# rpi_cm3plus_tablet.net
KiCad netlist of a schematic drawn in EAGLE
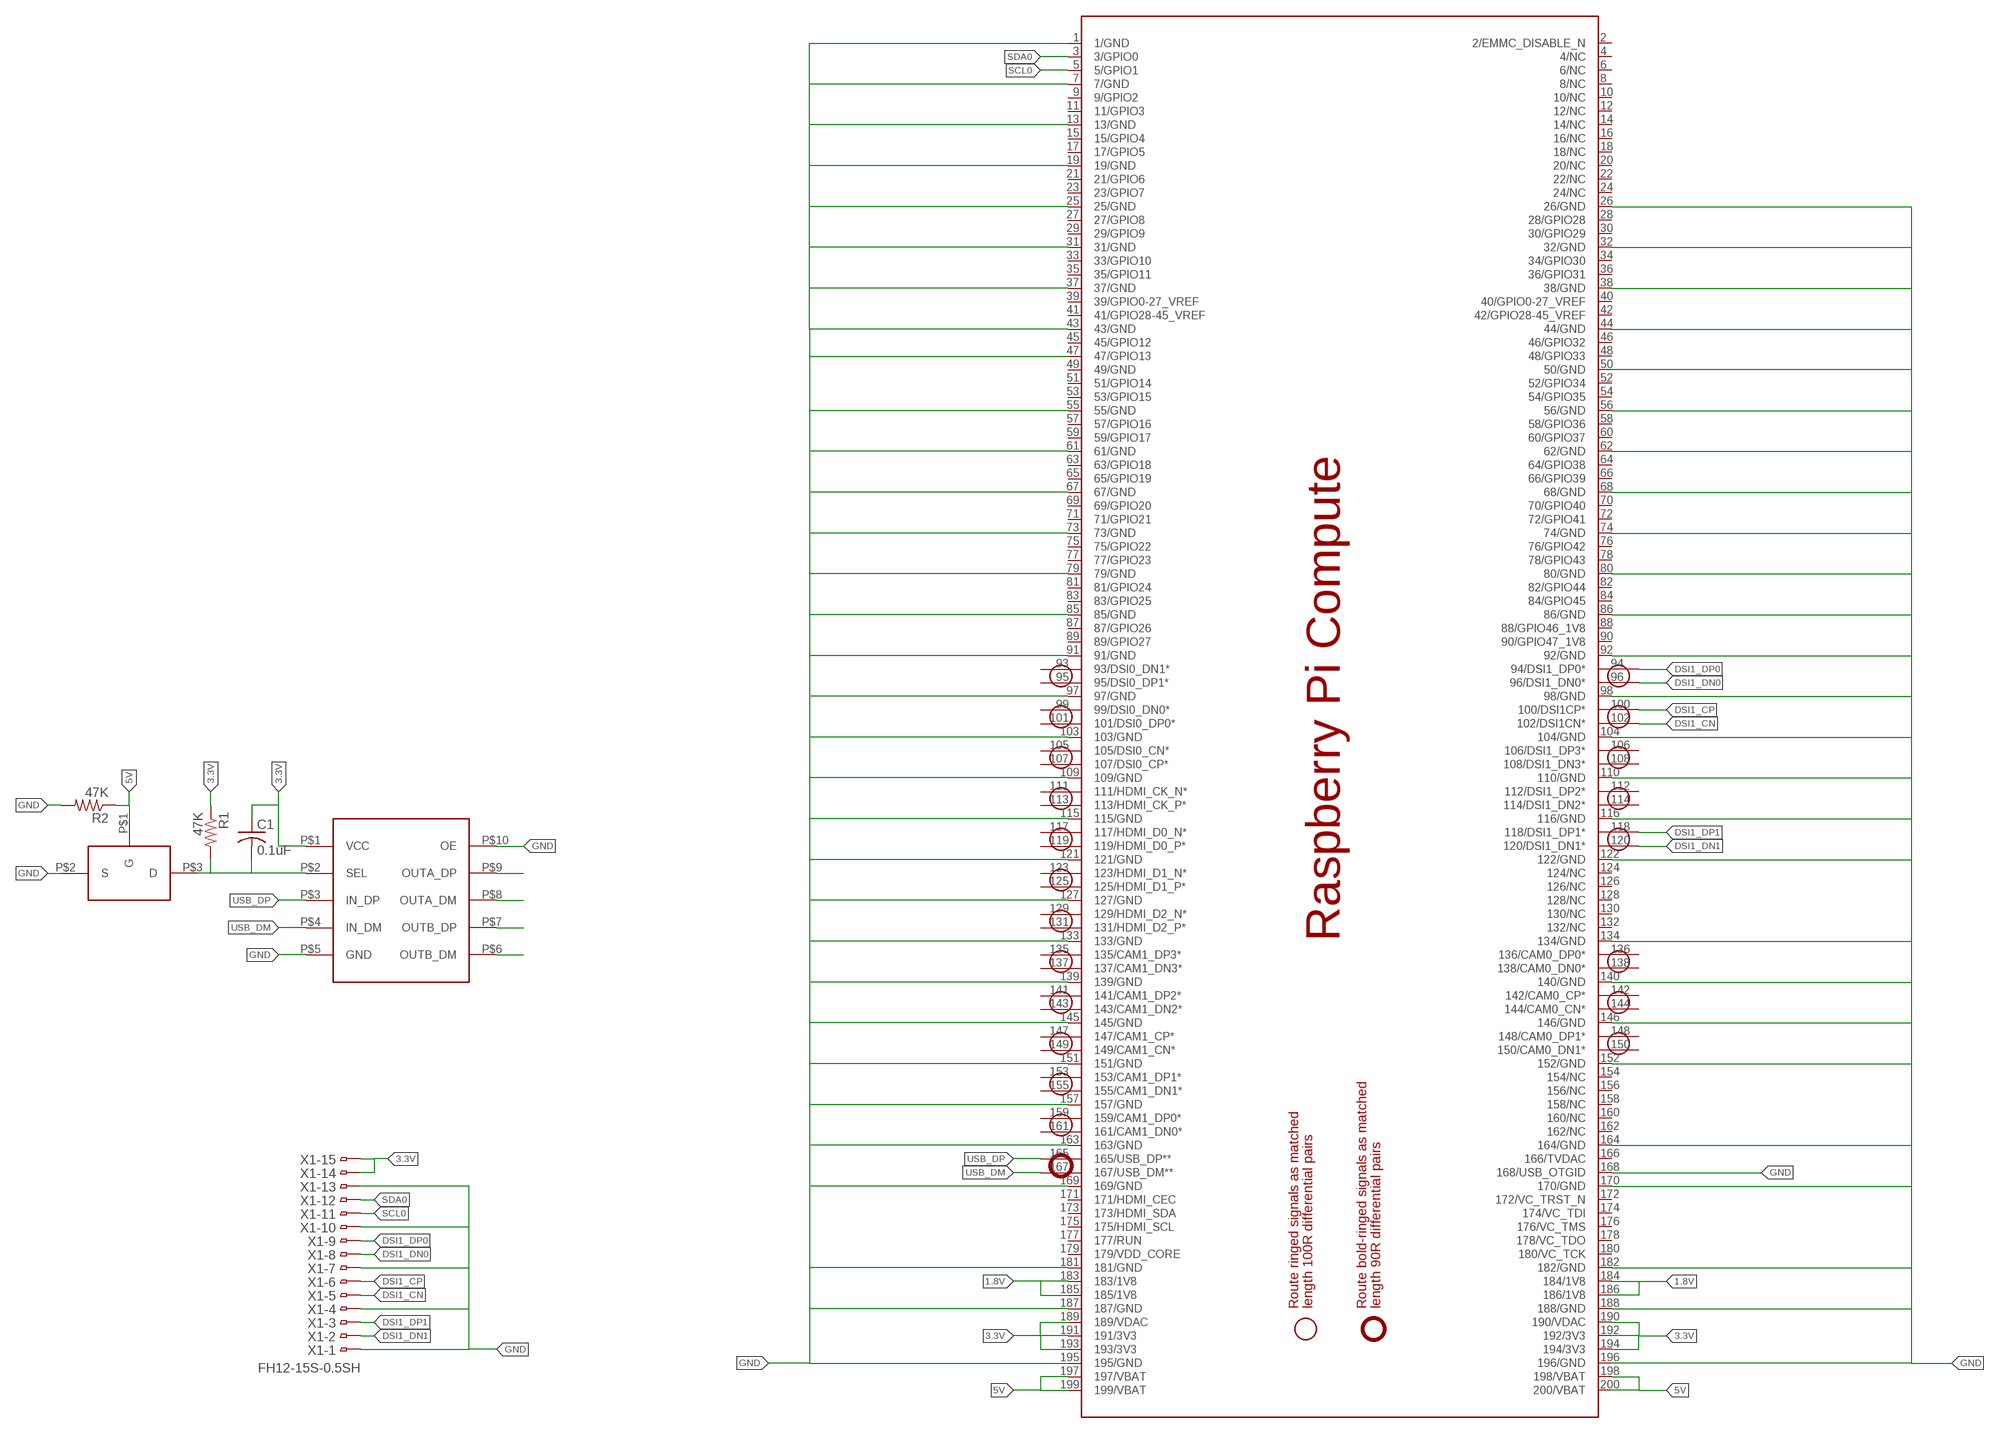
[diagram p0: schematic, sheet 1]

(export (version "E")
  (design (tool "Eeschema 10.0.6"))
  (components
    (comp (ref "C1")
      (value "0.1uF")
      (footprint "eagle-import:C0603K")
      (libsource (lib "eagle-import") (part "C-USC0603K"))
    )
    (comp (ref "PCB1")
      (value "RPI_COMPUTE")
      (footprint "eagle-import:RPI_COMPUTE")
      (libsource (lib "eagle-import") (part "RPI_COMPUTE"))
    )
    (comp (ref "R1")
      (value "47K")
      (footprint "eagle-import:R0603")
      (libsource (lib "eagle-import") (part "R-US_R0603"))
    )
    (comp (ref "R2")
      (value "47K")
      (footprint "eagle-import:R0603")
      (libsource (lib "eagle-import") (part "R-US_R0603"))
    )
    (comp (ref "U$1")
      (value "FSUSB42MUX")
      (footprint "eagle-import:MSOP-10")
      (libsource (lib "eagle-import") (part "FSUSB42MUX"))
    )
    (comp (ref "U$2")
      (value "BSS138-N")
      (footprint "eagle-import:SOT-23")
      (libsource (lib "eagle-import") (part "BSS138-N"))
    )
    (comp (ref "X1")
      (value "FH12-15S-0.5SH")
      (footprint "eagle-import:FH12-15S-0.5SH")
      (libsource (lib "eagle-import") (part "FH12-15S-0.5SH"))
    )
  )
  (nets
    (net (code "1") (name "1.8V") (class "Default")
      (node (ref "PCB1") (pin "183") (pinfunction "183/1V8_183") (pintype "bidirectional"))
      (node (ref "PCB1") (pin "184") (pinfunction "184/1V8_184") (pintype "bidirectional"))
      (node (ref "PCB1") (pin "185") (pinfunction "185/1V8_185") (pintype "bidirectional"))
      (node (ref "PCB1") (pin "186") (pinfunction "186/1V8_186") (pintype "bidirectional"))
    )
    (net (code "2") (name "3.3V") (class "Default")
      (node (ref "C1") (pin "1") (pinfunction "1_1") (pintype "passive"))
      (node (ref "PCB1") (pin "189") (pinfunction "189/VDAC_189") (pintype "bidirectional"))
      (node (ref "PCB1") (pin "190") (pinfunction "190/VDAC_190") (pintype "bidirectional"))
      (node (ref "PCB1") (pin "191") (pinfunction "191/3V3_191") (pintype "bidirectional"))
      (node (ref "PCB1") (pin "192") (pinfunction "192/3V3_192") (pintype "bidirectional"))
      (node (ref "PCB1") (pin "193") (pinfunction "193/3V3_193") (pintype "bidirectional"))
      (node (ref "PCB1") (pin "194") (pinfunction "194/3V3_194") (pintype "bidirectional"))
      (node (ref "R1") (pin "1") (pinfunction "1_1") (pintype "passive"))
      (node (ref "U$1") (pin "P$1") (pinfunction "VCC_P$1") (pintype "bidirectional"))
      (node (ref "X1") (pin "14") (pinfunction "1_14") (pintype "passive"))
      (node (ref "X1") (pin "15") (pinfunction "1_15") (pintype "passive"))
    )
    (net (code "3") (name "5V") (class "Default")
      (node (ref "PCB1") (pin "197") (pinfunction "197/VBAT_197") (pintype "bidirectional"))
      (node (ref "PCB1") (pin "198") (pinfunction "198/VBAT_198") (pintype "bidirectional"))
      (node (ref "PCB1") (pin "199") (pinfunction "199/VBAT_199") (pintype "bidirectional"))
      (node (ref "PCB1") (pin "200") (pinfunction "200/VBAT_200") (pintype "bidirectional"))
      (node (ref "R2") (pin "1") (pinfunction "1_1") (pintype "passive"))
      (node (ref "U$2") (pin "P$1") (pinfunction "G_P$1") (pintype "bidirectional"))
    )
    (net (code "4") (name "DSI1_CN") (class "Default")
      (node (ref "PCB1") (pin "102") (pinfunction "102/DSI1CN*_102") (pintype "bidirectional"))
      (node (ref "X1") (pin "5") (pinfunction "1_5") (pintype "passive"))
    )
    (net (code "5") (name "DSI1_CP") (class "Default")
      (node (ref "PCB1") (pin "100") (pinfunction "100/DSI1CP*_100") (pintype "bidirectional"))
      (node (ref "X1") (pin "6") (pinfunction "1_6") (pintype "passive"))
    )
    (net (code "6") (name "DSI1_DN0") (class "Default")
      (node (ref "PCB1") (pin "96") (pinfunction "96/DSI1_DN0*_96") (pintype "bidirectional"))
      (node (ref "X1") (pin "8") (pinfunction "1_8") (pintype "passive"))
    )
    (net (code "7") (name "DSI1_DN1") (class "Default")
      (node (ref "PCB1") (pin "120") (pinfunction "120/DSI1_DN1*_120") (pintype "bidirectional"))
      (node (ref "X1") (pin "2") (pinfunction "1_2") (pintype "passive"))
    )
    (net (code "8") (name "DSI1_DP0") (class "Default")
      (node (ref "PCB1") (pin "94") (pinfunction "94/DSI1_DP0*_94") (pintype "bidirectional"))
      (node (ref "X1") (pin "9") (pinfunction "1_9") (pintype "passive"))
    )
    (net (code "9") (name "DSI1_DP1") (class "Default")
      (node (ref "PCB1") (pin "118") (pinfunction "118/DSI1_DP1*_118") (pintype "bidirectional"))
      (node (ref "X1") (pin "3") (pinfunction "1_3") (pintype "passive"))
    )
    (net (code "10") (name "GND") (class "Default")
      (node (ref "PCB1") (pin "1") (pinfunction "1/GND_1") (pintype "bidirectional"))
      (node (ref "PCB1") (pin "103") (pinfunction "103/GND_103") (pintype "bidirectional"))
      (node (ref "PCB1") (pin "104") (pinfunction "104/GND_104") (pintype "bidirectional"))
      (node (ref "PCB1") (pin "109") (pinfunction "109/GND_109") (pintype "bidirectional"))
      (node (ref "PCB1") (pin "110") (pinfunction "110/GND_110") (pintype "bidirectional"))
      (node (ref "PCB1") (pin "115") (pinfunction "115/GND_115") (pintype "bidirectional"))
      (node (ref "PCB1") (pin "116") (pinfunction "116/GND_116") (pintype "bidirectional"))
      (node (ref "PCB1") (pin "121") (pinfunction "121/GND_121") (pintype "bidirectional"))
      (node (ref "PCB1") (pin "122") (pinfunction "122/GND_122") (pintype "bidirectional"))
      (node (ref "PCB1") (pin "127") (pinfunction "127/GND_127") (pintype "bidirectional"))
      (node (ref "PCB1") (pin "13") (pinfunction "13/GND_13") (pintype "bidirectional"))
      (node (ref "PCB1") (pin "133") (pinfunction "133/GND_133") (pintype "bidirectional"))
      (node (ref "PCB1") (pin "134") (pinfunction "134/GND_134") (pintype "bidirectional"))
      (node (ref "PCB1") (pin "139") (pinfunction "139/GND_139") (pintype "bidirectional"))
      (node (ref "PCB1") (pin "140") (pinfunction "140/GND_140") (pintype "bidirectional"))
      (node (ref "PCB1") (pin "145") (pinfunction "145/GND_145") (pintype "bidirectional"))
      (node (ref "PCB1") (pin "146") (pinfunction "146/GND_146") (pintype "bidirectional"))
      (node (ref "PCB1") (pin "151") (pinfunction "151/GND_151") (pintype "bidirectional"))
      (node (ref "PCB1") (pin "152") (pinfunction "152/GND_152") (pintype "bidirectional"))
      (node (ref "PCB1") (pin "157") (pinfunction "157/GND_157") (pintype "bidirectional"))
      (node (ref "PCB1") (pin "163") (pinfunction "163/GND_163") (pintype "bidirectional"))
      (node (ref "PCB1") (pin "164") (pinfunction "164/GND_164") (pintype "bidirectional"))
      (node (ref "PCB1") (pin "168") (pinfunction "168/USB_OTGID_168") (pintype "bidirectional"))
      (node (ref "PCB1") (pin "169") (pinfunction "169/GND_169") (pintype "bidirectional"))
      (node (ref "PCB1") (pin "170") (pinfunction "170/GND_170") (pintype "bidirectional"))
      (node (ref "PCB1") (pin "181") (pinfunction "181/GND_181") (pintype "bidirectional"))
      (node (ref "PCB1") (pin "182") (pinfunction "182/GND_182") (pintype "bidirectional"))
      (node (ref "PCB1") (pin "187") (pinfunction "187/GND_187") (pintype "bidirectional"))
      (node (ref "PCB1") (pin "188") (pinfunction "188/GND_188") (pintype "bidirectional"))
      (node (ref "PCB1") (pin "19") (pinfunction "19/GND_19") (pintype "bidirectional"))
      (node (ref "PCB1") (pin "195") (pinfunction "195/GND_195") (pintype "bidirectional"))
      (node (ref "PCB1") (pin "196") (pinfunction "196/GND_196") (pintype "bidirectional"))
      (node (ref "PCB1") (pin "25") (pinfunction "25/GND_25") (pintype "bidirectional"))
      (node (ref "PCB1") (pin "26") (pinfunction "26/GND_26") (pintype "bidirectional"))
      (node (ref "PCB1") (pin "31") (pinfunction "31/GND_31") (pintype "bidirectional"))
      (node (ref "PCB1") (pin "32") (pinfunction "32/GND_32") (pintype "bidirectional"))
      (node (ref "PCB1") (pin "37") (pinfunction "37/GND_37") (pintype "bidirectional"))
      (node (ref "PCB1") (pin "38") (pinfunction "38/GND_38") (pintype "bidirectional"))
      (node (ref "PCB1") (pin "43") (pinfunction "43/GND_43") (pintype "bidirectional"))
      (node (ref "PCB1") (pin "44") (pinfunction "44/GND_44") (pintype "bidirectional"))
      (node (ref "PCB1") (pin "47") (pinfunction "47/GPIO13_47") (pintype "bidirectional"))
      (node (ref "PCB1") (pin "50") (pinfunction "50/GND_50") (pintype "bidirectional"))
      (node (ref "PCB1") (pin "55") (pinfunction "55/GND_55") (pintype "bidirectional"))
      (node (ref "PCB1") (pin "56") (pinfunction "56/GND_56") (pintype "bidirectional"))
      (node (ref "PCB1") (pin "61") (pinfunction "61/GND_61") (pintype "bidirectional"))
      (node (ref "PCB1") (pin "62") (pinfunction "62/GND_62") (pintype "bidirectional"))
      (node (ref "PCB1") (pin "67") (pinfunction "67/GND_67") (pintype "bidirectional"))
      (node (ref "PCB1") (pin "68") (pinfunction "68/GND_68") (pintype "bidirectional"))
      (node (ref "PCB1") (pin "7") (pinfunction "7/GND_7") (pintype "bidirectional"))
      (node (ref "PCB1") (pin "73") (pinfunction "73/GND_73") (pintype "bidirectional"))
      (node (ref "PCB1") (pin "74") (pinfunction "74/GND_74") (pintype "bidirectional"))
      (node (ref "PCB1") (pin "79") (pinfunction "79/GND_79") (pintype "bidirectional"))
      (node (ref "PCB1") (pin "80") (pinfunction "80/GND_80") (pintype "bidirectional"))
      (node (ref "PCB1") (pin "85") (pinfunction "85/GND_85") (pintype "bidirectional"))
      (node (ref "PCB1") (pin "86") (pinfunction "86/GND_86") (pintype "bidirectional"))
      (node (ref "PCB1") (pin "91") (pinfunction "91/GND_91") (pintype "bidirectional"))
      (node (ref "PCB1") (pin "92") (pinfunction "92/GND_92") (pintype "bidirectional"))
      (node (ref "PCB1") (pin "97") (pinfunction "97/GND_97") (pintype "bidirectional"))
      (node (ref "PCB1") (pin "98") (pinfunction "98/GND_98") (pintype "bidirectional"))
      (node (ref "R2") (pin "2") (pinfunction "2_2") (pintype "passive"))
      (node (ref "U$1") (pin "P$10") (pinfunction "OE_P$10") (pintype "bidirectional"))
      (node (ref "U$1") (pin "P$5") (pinfunction "GND_P$5") (pintype "bidirectional"))
      (node (ref "U$2") (pin "P$2") (pinfunction "S_P$2") (pintype "bidirectional"))
      (node (ref "X1") (pin "1") (pinfunction "1_1") (pintype "passive"))
      (node (ref "X1") (pin "10") (pinfunction "1_10") (pintype "passive"))
      (node (ref "X1") (pin "13") (pinfunction "1_13") (pintype "passive"))
      (node (ref "X1") (pin "4") (pinfunction "1_4") (pintype "passive"))
      (node (ref "X1") (pin "7") (pinfunction "1_7") (pintype "passive"))
    )
    (net (code "11") (name "Net-(U$1-SEL)") (class "Default")
      (node (ref "C1") (pin "2") (pinfunction "2_2") (pintype "passive"))
      (node (ref "R1") (pin "2") (pinfunction "2_2") (pintype "passive"))
      (node (ref "U$1") (pin "P$2") (pinfunction "SEL_P$2") (pintype "bidirectional"))
      (node (ref "U$2") (pin "P$3") (pinfunction "D_P$3") (pintype "bidirectional"))
    )
    (net (code "12") (name "SCL0") (class "Default")
      (node (ref "PCB1") (pin "5") (pinfunction "5/GPIO1_5") (pintype "bidirectional"))
      (node (ref "X1") (pin "11") (pinfunction "1_11") (pintype "passive"))
    )
    (net (code "13") (name "SDA0") (class "Default")
      (node (ref "PCB1") (pin "3") (pinfunction "3/GPIO0_3") (pintype "bidirectional"))
      (node (ref "X1") (pin "12") (pinfunction "1_12") (pintype "passive"))
    )
    (net (code "14") (name "USB_DM") (class "Default")
      (node (ref "PCB1") (pin "167") (pinfunction "167/USB_DM**_167") (pintype "bidirectional"))
      (node (ref "U$1") (pin "P$4") (pinfunction "IN_DM_P$4") (pintype "bidirectional"))
    )
    (net (code "15") (name "USB_DP") (class "Default")
      (node (ref "PCB1") (pin "165") (pinfunction "165/USB_DP**_165") (pintype "bidirectional"))
      (node (ref "U$1") (pin "P$3") (pinfunction "IN_DP_P$3") (pintype "bidirectional"))
    )
    (net (code "16") (name "unconnected-(PCB1-2{slash}EMMC_DISABLE_N-Pad2)") (class "Default")
      (node (ref "PCB1") (pin "2") (pinfunction "2/EMMC_DISABLE_N_2") (pintype "bidirectional"))
    )
    (net (code "17") (name "unconnected-(PCB1-4{slash}NC-Pad4)") (class "Default")
      (node (ref "PCB1") (pin "4") (pinfunction "4/NC_4") (pintype "bidirectional"))
    )
    (net (code "18") (name "unconnected-(PCB1-6{slash}NC-Pad6)") (class "Default")
      (node (ref "PCB1") (pin "6") (pinfunction "6/NC_6") (pintype "bidirectional"))
    )
    (net (code "19") (name "unconnected-(PCB1-8{slash}NC-Pad8)") (class "Default")
      (node (ref "PCB1") (pin "8") (pinfunction "8/NC_8") (pintype "bidirectional"))
    )
    (net (code "20") (name "unconnected-(PCB1-9{slash}GPIO2-Pad9)") (class "Default")
      (node (ref "PCB1") (pin "9") (pinfunction "9/GPIO2_9") (pintype "bidirectional"))
    )
    (net (code "21") (name "unconnected-(PCB1-10{slash}NC-Pad10)") (class "Default")
      (node (ref "PCB1") (pin "10") (pinfunction "10/NC_10") (pintype "bidirectional"))
    )
    (net (code "22") (name "unconnected-(PCB1-11{slash}GPIO3-Pad11)") (class "Default")
      (node (ref "PCB1") (pin "11") (pinfunction "11/GPIO3_11") (pintype "bidirectional"))
    )
    (net (code "23") (name "unconnected-(PCB1-12{slash}NC-Pad12)") (class "Default")
      (node (ref "PCB1") (pin "12") (pinfunction "12/NC_12") (pintype "bidirectional"))
    )
    (net (code "24") (name "unconnected-(PCB1-14{slash}NC-Pad14)") (class "Default")
      (node (ref "PCB1") (pin "14") (pinfunction "14/NC_14") (pintype "bidirectional"))
    )
    (net (code "25") (name "unconnected-(PCB1-15{slash}GPIO4-Pad15)") (class "Default")
      (node (ref "PCB1") (pin "15") (pinfunction "15/GPIO4_15") (pintype "bidirectional"))
    )
    (net (code "26") (name "unconnected-(PCB1-16{slash}NC-Pad16)") (class "Default")
      (node (ref "PCB1") (pin "16") (pinfunction "16/NC_16") (pintype "bidirectional"))
    )
    (net (code "27") (name "unconnected-(PCB1-17{slash}GPIO5-Pad17)") (class "Default")
      (node (ref "PCB1") (pin "17") (pinfunction "17/GPIO5_17") (pintype "bidirectional"))
    )
    (net (code "28") (name "unconnected-(PCB1-18{slash}NC-Pad18)") (class "Default")
      (node (ref "PCB1") (pin "18") (pinfunction "18/NC_18") (pintype "bidirectional"))
    )
    (net (code "29") (name "unconnected-(PCB1-20{slash}NC-Pad20)") (class "Default")
      (node (ref "PCB1") (pin "20") (pinfunction "20/NC_20") (pintype "bidirectional"))
    )
    (net (code "30") (name "unconnected-(PCB1-21{slash}GPIO6-Pad21)") (class "Default")
      (node (ref "PCB1") (pin "21") (pinfunction "21/GPIO6_21") (pintype "bidirectional"))
    )
    (net (code "31") (name "unconnected-(PCB1-22{slash}NC-Pad22)") (class "Default")
      (node (ref "PCB1") (pin "22") (pinfunction "22/NC_22") (pintype "bidirectional"))
    )
    (net (code "32") (name "unconnected-(PCB1-23{slash}GPIO7-Pad23)") (class "Default")
      (node (ref "PCB1") (pin "23") (pinfunction "23/GPIO7_23") (pintype "bidirectional"))
    )
    (net (code "33") (name "unconnected-(PCB1-24{slash}NC-Pad24)") (class "Default")
      (node (ref "PCB1") (pin "24") (pinfunction "24/NC_24") (pintype "bidirectional"))
    )
    (net (code "34") (name "unconnected-(PCB1-27{slash}GPIO8-Pad27)") (class "Default")
      (node (ref "PCB1") (pin "27") (pinfunction "27/GPIO8_27") (pintype "bidirectional"))
    )
    (net (code "35") (name "unconnected-(PCB1-28{slash}GPIO28-Pad28)") (class "Default")
      (node (ref "PCB1") (pin "28") (pinfunction "28/GPIO28_28") (pintype "bidirectional"))
    )
    (net (code "36") (name "unconnected-(PCB1-29{slash}GPIO9-Pad29)") (class "Default")
      (node (ref "PCB1") (pin "29") (pinfunction "29/GPIO9_29") (pintype "bidirectional"))
    )
    (net (code "37") (name "unconnected-(PCB1-30{slash}GPIO29-Pad30)") (class "Default")
      (node (ref "PCB1") (pin "30") (pinfunction "30/GPIO29_30") (pintype "bidirectional"))
    )
    (net (code "38") (name "unconnected-(PCB1-33{slash}GPIO10-Pad33)") (class "Default")
      (node (ref "PCB1") (pin "33") (pinfunction "33/GPIO10_33") (pintype "bidirectional"))
    )
    (net (code "39") (name "unconnected-(PCB1-34{slash}GPIO30-Pad34)") (class "Default")
      (node (ref "PCB1") (pin "34") (pinfunction "34/GPIO30_34") (pintype "bidirectional"))
    )
    (net (code "40") (name "unconnected-(PCB1-35{slash}GPIO11-Pad35)") (class "Default")
      (node (ref "PCB1") (pin "35") (pinfunction "35/GPIO11_35") (pintype "bidirectional"))
    )
    (net (code "41") (name "unconnected-(PCB1-36{slash}GPIO31-Pad36)") (class "Default")
      (node (ref "PCB1") (pin "36") (pinfunction "36/GPIO31_36") (pintype "bidirectional"))
    )
    (net (code "42") (name "unconnected-(PCB1-39{slash}GPIO0-27_VREF-Pad39)") (class "Default")
      (node (ref "PCB1") (pin "39") (pinfunction "39/GPIO0-27_VREF_39") (pintype "bidirectional"))
    )
    (net (code "43") (name "unconnected-(PCB1-40{slash}GPIO0-27_VREF-Pad40)") (class "Default")
      (node (ref "PCB1") (pin "40") (pinfunction "40/GPIO0-27_VREF_40") (pintype "bidirectional"))
    )
    (net (code "44") (name "unconnected-(PCB1-41{slash}GPIO28-45_VREF-Pad41)") (class "Default")
      (node (ref "PCB1") (pin "41") (pinfunction "41/GPIO28-45_VREF_41") (pintype "bidirectional"))
    )
    (net (code "45") (name "unconnected-(PCB1-42{slash}GPIO28-45_VREF-Pad42)") (class "Default")
      (node (ref "PCB1") (pin "42") (pinfunction "42/GPIO28-45_VREF_42") (pintype "bidirectional"))
    )
    (net (code "46") (name "unconnected-(PCB1-45{slash}GPIO12-Pad45)") (class "Default")
      (node (ref "PCB1") (pin "45") (pinfunction "45/GPIO12_45") (pintype "bidirectional"))
    )
    (net (code "47") (name "unconnected-(PCB1-46{slash}GPIO32-Pad46)") (class "Default")
      (node (ref "PCB1") (pin "46") (pinfunction "46/GPIO32_46") (pintype "bidirectional"))
    )
    (net (code "48") (name "unconnected-(PCB1-48{slash}GPIO33-Pad48)") (class "Default")
      (node (ref "PCB1") (pin "48") (pinfunction "48/GPIO33_48") (pintype "bidirectional"))
    )
    (net (code "49") (name "unconnected-(PCB1-49{slash}GND-Pad49)") (class "Default")
      (node (ref "PCB1") (pin "49") (pinfunction "49/GND_49") (pintype "bidirectional"))
    )
    (net (code "50") (name "unconnected-(PCB1-51{slash}GPIO14-Pad51)") (class "Default")
      (node (ref "PCB1") (pin "51") (pinfunction "51/GPIO14_51") (pintype "bidirectional"))
    )
    (net (code "51") (name "unconnected-(PCB1-52{slash}GPIO34-Pad52)") (class "Default")
      (node (ref "PCB1") (pin "52") (pinfunction "52/GPIO34_52") (pintype "bidirectional"))
    )
    (net (code "52") (name "unconnected-(PCB1-53{slash}GPIO15-Pad53)") (class "Default")
      (node (ref "PCB1") (pin "53") (pinfunction "53/GPIO15_53") (pintype "bidirectional"))
    )
    (net (code "53") (name "unconnected-(PCB1-54{slash}GPIO35-Pad54)") (class "Default")
      (node (ref "PCB1") (pin "54") (pinfunction "54/GPIO35_54") (pintype "bidirectional"))
    )
    (net (code "54") (name "unconnected-(PCB1-57{slash}GPIO16-Pad57)") (class "Default")
      (node (ref "PCB1") (pin "57") (pinfunction "57/GPIO16_57") (pintype "bidirectional"))
    )
    (net (code "55") (name "unconnected-(PCB1-58{slash}GPIO36-Pad58)") (class "Default")
      (node (ref "PCB1") (pin "58") (pinfunction "58/GPIO36_58") (pintype "bidirectional"))
    )
    (net (code "56") (name "unconnected-(PCB1-59{slash}GPIO17-Pad59)") (class "Default")
      (node (ref "PCB1") (pin "59") (pinfunction "59/GPIO17_59") (pintype "bidirectional"))
    )
    (net (code "57") (name "unconnected-(PCB1-60{slash}GPIO37-Pad60)") (class "Default")
      (node (ref "PCB1") (pin "60") (pinfunction "60/GPIO37_60") (pintype "bidirectional"))
    )
    (net (code "58") (name "unconnected-(PCB1-63{slash}GPIO18-Pad63)") (class "Default")
      (node (ref "PCB1") (pin "63") (pinfunction "63/GPIO18_63") (pintype "bidirectional"))
    )
    (net (code "59") (name "unconnected-(PCB1-64{slash}GPIO38-Pad64)") (class "Default")
      (node (ref "PCB1") (pin "64") (pinfunction "64/GPIO38_64") (pintype "bidirectional"))
    )
    (net (code "60") (name "unconnected-(PCB1-65{slash}GPIO19-Pad65)") (class "Default")
      (node (ref "PCB1") (pin "65") (pinfunction "65/GPIO19_65") (pintype "bidirectional"))
    )
    (net (code "61") (name "unconnected-(PCB1-66{slash}GPIO39-Pad66)") (class "Default")
      (node (ref "PCB1") (pin "66") (pinfunction "66/GPIO39_66") (pintype "bidirectional"))
    )
    (net (code "62") (name "unconnected-(PCB1-69{slash}GPIO20-Pad69)") (class "Default")
      (node (ref "PCB1") (pin "69") (pinfunction "69/GPIO20_69") (pintype "bidirectional"))
    )
    (net (code "63") (name "unconnected-(PCB1-70{slash}GPIO40-Pad70)") (class "Default")
      (node (ref "PCB1") (pin "70") (pinfunction "70/GPIO40_70") (pintype "bidirectional"))
    )
    (net (code "64") (name "unconnected-(PCB1-71{slash}GPIO21-Pad71)") (class "Default")
      (node (ref "PCB1") (pin "71") (pinfunction "71/GPIO21_71") (pintype "bidirectional"))
    )
    (net (code "65") (name "unconnected-(PCB1-72{slash}GPIO41-Pad72)") (class "Default")
      (node (ref "PCB1") (pin "72") (pinfunction "72/GPIO41_72") (pintype "bidirectional"))
    )
    (net (code "66") (name "unconnected-(PCB1-75{slash}GPIO22-Pad75)") (class "Default")
      (node (ref "PCB1") (pin "75") (pinfunction "75/GPIO22_75") (pintype "bidirectional"))
    )
    (net (code "67") (name "unconnected-(PCB1-76{slash}GPIO42-Pad76)") (class "Default")
      (node (ref "PCB1") (pin "76") (pinfunction "76/GPIO42_76") (pintype "bidirectional"))
    )
    (net (code "68") (name "unconnected-(PCB1-77{slash}GPIO23-Pad77)") (class "Default")
      (node (ref "PCB1") (pin "77") (pinfunction "77/GPIO23_77") (pintype "bidirectional"))
    )
    (net (code "69") (name "unconnected-(PCB1-78{slash}GPIO43-Pad78)") (class "Default")
      (node (ref "PCB1") (pin "78") (pinfunction "78/GPIO43_78") (pintype "bidirectional"))
    )
    (net (code "70") (name "unconnected-(PCB1-81{slash}GPIO24-Pad81)") (class "Default")
      (node (ref "PCB1") (pin "81") (pinfunction "81/GPIO24_81") (pintype "bidirectional"))
    )
    (net (code "71") (name "unconnected-(PCB1-82{slash}GPIO44-Pad82)") (class "Default")
      (node (ref "PCB1") (pin "82") (pinfunction "82/GPIO44_82") (pintype "bidirectional"))
    )
    (net (code "72") (name "unconnected-(PCB1-83{slash}GPIO25-Pad83)") (class "Default")
      (node (ref "PCB1") (pin "83") (pinfunction "83/GPIO25_83") (pintype "bidirectional"))
    )
    (net (code "73") (name "unconnected-(PCB1-84{slash}GPIO45-Pad84)") (class "Default")
      (node (ref "PCB1") (pin "84") (pinfunction "84/GPIO45_84") (pintype "bidirectional"))
    )
    (net (code "74") (name "unconnected-(PCB1-87{slash}GPIO26-Pad87)") (class "Default")
      (node (ref "PCB1") (pin "87") (pinfunction "87/GPIO26_87") (pintype "bidirectional"))
    )
    (net (code "75") (name "unconnected-(PCB1-88{slash}GPIO46_1V8-Pad88)") (class "Default")
      (node (ref "PCB1") (pin "88") (pinfunction "88/GPIO46_1V8_88") (pintype "bidirectional"))
    )
    (net (code "76") (name "unconnected-(PCB1-89{slash}GPIO27-Pad89)") (class "Default")
      (node (ref "PCB1") (pin "89") (pinfunction "89/GPIO27_89") (pintype "bidirectional"))
    )
    (net (code "77") (name "unconnected-(PCB1-90{slash}GPIO47_1V8-Pad90)") (class "Default")
      (node (ref "PCB1") (pin "90") (pinfunction "90/GPIO47_1V8_90") (pintype "bidirectional"))
    )
    (net (code "78") (name "unconnected-(PCB1-93{slash}DSI0_DN1*-Pad93)") (class "Default")
      (node (ref "PCB1") (pin "93") (pinfunction "93/DSI0_DN1*_93") (pintype "bidirectional"))
    )
    (net (code "79") (name "unconnected-(PCB1-95{slash}DSI0_DP1*-Pad95)") (class "Default")
      (node (ref "PCB1") (pin "95") (pinfunction "95/DSI0_DP1*_95") (pintype "bidirectional"))
    )
    (net (code "80") (name "unconnected-(PCB1-99{slash}DSI0_DN0*-Pad99)") (class "Default")
      (node (ref "PCB1") (pin "99") (pinfunction "99/DSI0_DN0*_99") (pintype "bidirectional"))
    )
    (net (code "81") (name "unconnected-(PCB1-101{slash}DSI0_DP0*-Pad101)") (class "Default")
      (node (ref "PCB1") (pin "101") (pinfunction "101/DSI0_DP0*_101") (pintype "bidirectional"))
    )
    (net (code "82") (name "unconnected-(PCB1-105{slash}DSI0_CN*-Pad105)") (class "Default")
      (node (ref "PCB1") (pin "105") (pinfunction "105/DSI0_CN*_105") (pintype "bidirectional"))
    )
    (net (code "83") (name "unconnected-(PCB1-106{slash}DSI1_DP3*-Pad106)") (class "Default")
      (node (ref "PCB1") (pin "106") (pinfunction "106/DSI1_DP3*_106") (pintype "bidirectional"))
    )
    (net (code "84") (name "unconnected-(PCB1-107{slash}DSI0_CP*-Pad107)") (class "Default")
      (node (ref "PCB1") (pin "107") (pinfunction "107/DSI0_CP*_107") (pintype "bidirectional"))
    )
    (net (code "85") (name "unconnected-(PCB1-108{slash}DSI1_DN3*-Pad108)") (class "Default")
      (node (ref "PCB1") (pin "108") (pinfunction "108/DSI1_DN3*_108") (pintype "bidirectional"))
    )
    (net (code "86") (name "unconnected-(PCB1-111{slash}HDMI_CK_N*-Pad111)") (class "Default")
      (node (ref "PCB1") (pin "111") (pinfunction "111/HDMI_CK_N*_111") (pintype "bidirectional"))
    )
    (net (code "87") (name "unconnected-(PCB1-112{slash}DSI1_DP2*-Pad112)") (class "Default")
      (node (ref "PCB1") (pin "112") (pinfunction "112/DSI1_DP2*_112") (pintype "bidirectional"))
    )
    (net (code "88") (name "unconnected-(PCB1-113{slash}HDMI_CK_P*-Pad113)") (class "Default")
      (node (ref "PCB1") (pin "113") (pinfunction "113/HDMI_CK_P*_113") (pintype "bidirectional"))
    )
    (net (code "89") (name "unconnected-(PCB1-114{slash}DSI1_DN2*-Pad114)") (class "Default")
      (node (ref "PCB1") (pin "114") (pinfunction "114/DSI1_DN2*_114") (pintype "bidirectional"))
    )
    (net (code "90") (name "unconnected-(PCB1-117{slash}HDMI_D0_N*-Pad117)") (class "Default")
      (node (ref "PCB1") (pin "117") (pinfunction "117/HDMI_D0_N*_117") (pintype "bidirectional"))
    )
    (net (code "91") (name "unconnected-(PCB1-119{slash}HDMI_D0_P*-Pad119)") (class "Default")
      (node (ref "PCB1") (pin "119") (pinfunction "119/HDMI_D0_P*_119") (pintype "bidirectional"))
    )
    (net (code "92") (name "unconnected-(PCB1-123{slash}HDMI_D1_N*-Pad123)") (class "Default")
      (node (ref "PCB1") (pin "123") (pinfunction "123/HDMI_D1_N*_123") (pintype "bidirectional"))
    )
    (net (code "93") (name "unconnected-(PCB1-124{slash}NC-Pad124)") (class "Default")
      (node (ref "PCB1") (pin "124") (pinfunction "124/NC_124") (pintype "bidirectional"))
    )
    (net (code "94") (name "unconnected-(PCB1-125{slash}HDMI_D1_P*-Pad125)") (class "Default")
      (node (ref "PCB1") (pin "125") (pinfunction "125/HDMI_D1_P*_125") (pintype "bidirectional"))
    )
    (net (code "95") (name "unconnected-(PCB1-126{slash}NC-Pad126)") (class "Default")
      (node (ref "PCB1") (pin "126") (pinfunction "126/NC_126") (pintype "bidirectional"))
    )
    (net (code "96") (name "unconnected-(PCB1-128{slash}NC-Pad128)") (class "Default")
      (node (ref "PCB1") (pin "128") (pinfunction "128/NC_128") (pintype "bidirectional"))
    )
    (net (code "97") (name "unconnected-(PCB1-129{slash}HDMI_D2_N*-Pad129)") (class "Default")
      (node (ref "PCB1") (pin "129") (pinfunction "129/HDMI_D2_N*_129") (pintype "bidirectional"))
    )
    (net (code "98") (name "unconnected-(PCB1-130{slash}NC-Pad130)") (class "Default")
      (node (ref "PCB1") (pin "130") (pinfunction "130/NC_130") (pintype "bidirectional"))
    )
    (net (code "99") (name "unconnected-(PCB1-131{slash}HDMI_D2_P*-Pad131)") (class "Default")
      (node (ref "PCB1") (pin "131") (pinfunction "131/HDMI_D2_P*_131") (pintype "bidirectional"))
    )
    (net (code "100") (name "unconnected-(PCB1-132{slash}NC-Pad132)") (class "Default")
      (node (ref "PCB1") (pin "132") (pinfunction "132/NC_132") (pintype "bidirectional"))
    )
    (net (code "101") (name "unconnected-(PCB1-135{slash}CAM1_DP3*-Pad135)") (class "Default")
      (node (ref "PCB1") (pin "135") (pinfunction "135/CAM1_DP3*_135") (pintype "bidirectional"))
    )
    (net (code "102") (name "unconnected-(PCB1-136{slash}CAM0_DP0*-Pad136)") (class "Default")
      (node (ref "PCB1") (pin "136") (pinfunction "136/CAM0_DP0*_136") (pintype "bidirectional"))
    )
    (net (code "103") (name "unconnected-(PCB1-137{slash}CAM1_DN3*-Pad137)") (class "Default")
      (node (ref "PCB1") (pin "137") (pinfunction "137/CAM1_DN3*_137") (pintype "bidirectional"))
    )
    (net (code "104") (name "unconnected-(PCB1-138{slash}CAM0_DN0*-Pad138)") (class "Default")
      (node (ref "PCB1") (pin "138") (pinfunction "138/CAM0_DN0*_138") (pintype "bidirectional"))
    )
    (net (code "105") (name "unconnected-(PCB1-141{slash}CAM1_DP2*-Pad141)") (class "Default")
      (node (ref "PCB1") (pin "141") (pinfunction "141/CAM1_DP2*_141") (pintype "bidirectional"))
    )
    (net (code "106") (name "unconnected-(PCB1-142{slash}CAM0_CP*-Pad142)") (class "Default")
      (node (ref "PCB1") (pin "142") (pinfunction "142/CAM0_CP*_142") (pintype "bidirectional"))
    )
    (net (code "107") (name "unconnected-(PCB1-143{slash}CAM1_DN2*-Pad143)") (class "Default")
      (node (ref "PCB1") (pin "143") (pinfunction "143/CAM1_DN2*_143") (pintype "bidirectional"))
    )
    (net (code "108") (name "unconnected-(PCB1-144{slash}CAM0_CN*-Pad144)") (class "Default")
      (node (ref "PCB1") (pin "144") (pinfunction "144/CAM0_CN*_144") (pintype "bidirectional"))
    )
    (net (code "109") (name "unconnected-(PCB1-147{slash}CAM1_CP*-Pad147)") (class "Default")
      (node (ref "PCB1") (pin "147") (pinfunction "147/CAM1_CP*_147") (pintype "bidirectional"))
    )
    (net (code "110") (name "unconnected-(PCB1-148{slash}CAM0_DP1*-Pad148)") (class "Default")
      (node (ref "PCB1") (pin "148") (pinfunction "148/CAM0_DP1*_148") (pintype "bidirectional"))
    )
    (net (code "111") (name "unconnected-(PCB1-149{slash}CAM1_CN*-Pad149)") (class "Default")
      (node (ref "PCB1") (pin "149") (pinfunction "149/CAM1_CN*_149") (pintype "bidirectional"))
    )
    (net (code "112") (name "unconnected-(PCB1-150{slash}CAM0_DN1*-Pad150)") (class "Default")
      (node (ref "PCB1") (pin "150") (pinfunction "150/CAM0_DN1*_150") (pintype "bidirectional"))
    )
    (net (code "113") (name "unconnected-(PCB1-153{slash}CAM1_DP1*-Pad153)") (class "Default")
      (node (ref "PCB1") (pin "153") (pinfunction "153/CAM1_DP1*_153") (pintype "bidirectional"))
    )
    (net (code "114") (name "unconnected-(PCB1-154{slash}NC-Pad154)") (class "Default")
      (node (ref "PCB1") (pin "154") (pinfunction "154/NC_154") (pintype "bidirectional"))
    )
    (net (code "115") (name "unconnected-(PCB1-155{slash}CAM1_DN1*-Pad155)") (class "Default")
      (node (ref "PCB1") (pin "155") (pinfunction "155/CAM1_DN1*_155") (pintype "bidirectional"))
    )
    (net (code "116") (name "unconnected-(PCB1-156{slash}NC-Pad156)") (class "Default")
      (node (ref "PCB1") (pin "156") (pinfunction "156/NC_156") (pintype "bidirectional"))
    )
    (net (code "117") (name "unconnected-(PCB1-158{slash}NC-Pad158)") (class "Default")
      (node (ref "PCB1") (pin "158") (pinfunction "158/NC_158") (pintype "bidirectional"))
    )
    (net (code "118") (name "unconnected-(PCB1-159{slash}CAM1_DP0*-Pad159)") (class "Default")
      (node (ref "PCB1") (pin "159") (pinfunction "159/CAM1_DP0*_159") (pintype "bidirectional"))
    )
    (net (code "119") (name "unconnected-(PCB1-160{slash}NC-Pad160)") (class "Default")
      (node (ref "PCB1") (pin "160") (pinfunction "160/NC_160") (pintype "bidirectional"))
    )
    (net (code "120") (name "unconnected-(PCB1-161{slash}CAM1_DN0*-Pad161)") (class "Default")
      (node (ref "PCB1") (pin "161") (pinfunction "161/CAM1_DN0*_161") (pintype "bidirectional"))
    )
    (net (code "121") (name "unconnected-(PCB1-162{slash}NC-Pad162)") (class "Default")
      (node (ref "PCB1") (pin "162") (pinfunction "162/NC_162") (pintype "bidirectional"))
    )
    (net (code "122") (name "unconnected-(PCB1-166{slash}TVDAC-Pad166)") (class "Default")
      (node (ref "PCB1") (pin "166") (pinfunction "166/TVDAC_166") (pintype "bidirectional"))
    )
    (net (code "123") (name "unconnected-(PCB1-171{slash}HDMI_CEC-Pad171)") (class "Default")
      (node (ref "PCB1") (pin "171") (pinfunction "171/HDMI_CEC_171") (pintype "bidirectional"))
    )
    (net (code "124") (name "unconnected-(PCB1-172{slash}VC_TRST_N-Pad172)") (class "Default")
      (node (ref "PCB1") (pin "172") (pinfunction "172/VC_TRST_N_172") (pintype "bidirectional"))
    )
    (net (code "125") (name "unconnected-(PCB1-173{slash}HDMI_SDA-Pad173)") (class "Default")
      (node (ref "PCB1") (pin "173") (pinfunction "173/HDMI_SDA_173") (pintype "bidirectional"))
    )
    (net (code "126") (name "unconnected-(PCB1-174{slash}VC_TDI-Pad174)") (class "Default")
      (node (ref "PCB1") (pin "174") (pinfunction "174/VC_TDI_174") (pintype "bidirectional"))
    )
    (net (code "127") (name "unconnected-(PCB1-175{slash}HDMI_SCL-Pad175)") (class "Default")
      (node (ref "PCB1") (pin "175") (pinfunction "175/HDMI_SCL_175") (pintype "bidirectional"))
    )
    (net (code "128") (name "unconnected-(PCB1-176{slash}VC_TMS-Pad176)") (class "Default")
      (node (ref "PCB1") (pin "176") (pinfunction "176/VC_TMS_176") (pintype "bidirectional"))
    )
    (net (code "129") (name "unconnected-(PCB1-177{slash}RUN-Pad177)") (class "Default")
      (node (ref "PCB1") (pin "177") (pinfunction "177/RUN_177") (pintype "bidirectional"))
    )
    (net (code "130") (name "unconnected-(PCB1-178{slash}VC_TDO-Pad178)") (class "Default")
      (node (ref "PCB1") (pin "178") (pinfunction "178/VC_TDO_178") (pintype "bidirectional"))
    )
    (net (code "131") (name "unconnected-(PCB1-179{slash}VDD_CORE-Pad179)") (class "Default")
      (node (ref "PCB1") (pin "179") (pinfunction "179/VDD_CORE_179") (pintype "bidirectional"))
    )
    (net (code "132") (name "unconnected-(PCB1-180{slash}VC_TCK-Pad180)") (class "Default")
      (node (ref "PCB1") (pin "180") (pinfunction "180/VC_TCK_180") (pintype "bidirectional"))
    )
    (net (code "133") (name "unconnected-(U$1-OUTA_DM-PadP$8)") (class "Default")
      (node (ref "U$1") (pin "P$8") (pinfunction "OUTA_DM_P$8") (pintype "bidirectional"))
    )
    (net (code "134") (name "unconnected-(U$1-OUTA_DP-PadP$9)") (class "Default")
      (node (ref "U$1") (pin "P$9") (pinfunction "OUTA_DP_P$9") (pintype "bidirectional"))
    )
    (net (code "135") (name "unconnected-(U$1-OUTB_DM-PadP$6)") (class "Default")
      (node (ref "U$1") (pin "P$6") (pinfunction "OUTB_DM_P$6") (pintype "bidirectional"))
    )
    (net (code "136") (name "unconnected-(U$1-OUTB_DP-PadP$7)") (class "Default")
      (node (ref "U$1") (pin "P$7") (pinfunction "OUTB_DP_P$7") (pintype "bidirectional"))
    )
  )
)
